# Rolab_PDD_prot.net
KiCad netlist of a schematic drawn in EAGLE
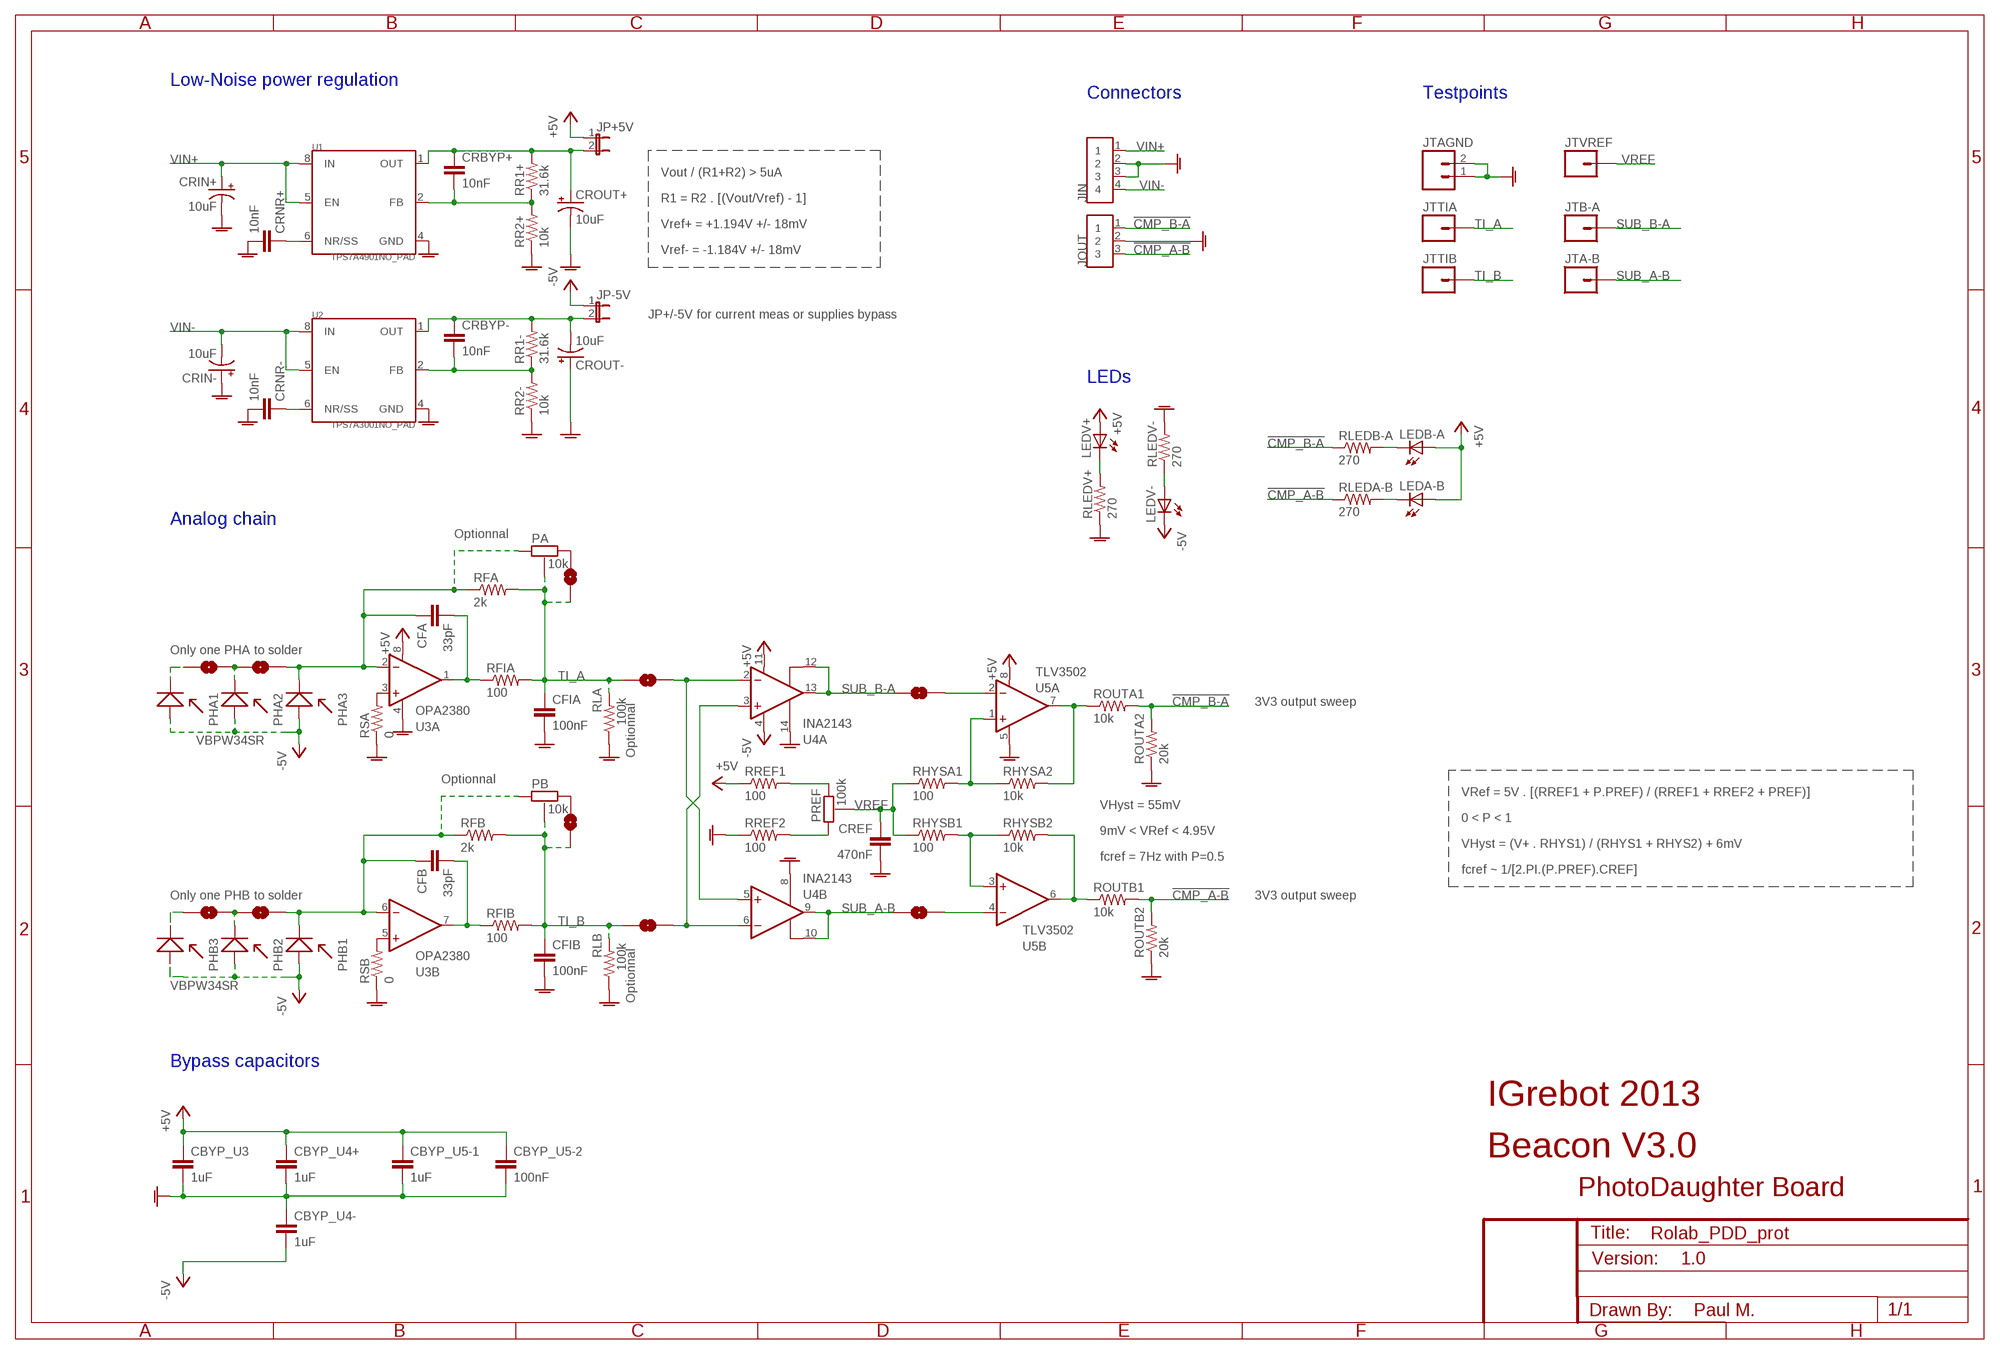
[diagram p0: schematic, sheet 1]

(export (version "E")
  (design (tool "Eeschema 10.0.6"))
  (components
    (comp (ref "CBYP_U3")
      (value "1uF")
      (footprint "eagle-import:0603-CAP")
      (libsource (lib "eagle-import") (part "CAP0603-CAP"))
    )
    (comp (ref "CBYP_U4+")
      (value "1uF")
      (footprint "eagle-import:0603-CAP")
      (libsource (lib "eagle-import") (part "CAP0603-CAP"))
    )
    (comp (ref "CBYP_U4-")
      (value "1uF")
      (footprint "eagle-import:0603-CAP")
      (libsource (lib "eagle-import") (part "CAP0603-CAP"))
    )
    (comp (ref "CBYP_U5-1")
      (value "1uF")
      (footprint "eagle-import:0603-CAP")
      (libsource (lib "eagle-import") (part "CAP0603-CAP"))
    )
    (comp (ref "CBYP_U5-2")
      (value "100nF")
      (footprint "eagle-import:0603-CAP")
      (libsource (lib "eagle-import") (part "CAP0603-CAP"))
    )
    (comp (ref "CFA")
      (value "33pF")
      (footprint "eagle-import:0603-CAP")
      (libsource (lib "eagle-import") (part "CAP0603-CAP"))
    )
    (comp (ref "CFB")
      (value "33pF")
      (footprint "eagle-import:0603-CAP")
      (libsource (lib "eagle-import") (part "CAP0603-CAP"))
    )
    (comp (ref "CFIA")
      (value "100nF")
      (footprint "eagle-import:0603-CAP")
      (libsource (lib "eagle-import") (part "CAP0603-CAP"))
    )
    (comp (ref "CFIB")
      (value "100nF")
      (footprint "eagle-import:0603-CAP")
      (libsource (lib "eagle-import") (part "CAP0603-CAP"))
    )
    (comp (ref "CRBYP+")
      (value "10nF")
      (footprint "eagle-import:0603-CAP")
      (libsource (lib "eagle-import") (part "CAP0603-CAP"))
    )
    (comp (ref "CRBYP-")
      (value "10nF")
      (footprint "eagle-import:0603-CAP")
      (libsource (lib "eagle-import") (part "CAP0603-CAP"))
    )
    (comp (ref "CREF")
      (value "470nF")
      (footprint "eagle-import:0603-CAP")
      (libsource (lib "eagle-import") (part "CAP0603-CAP"))
    )
    (comp (ref "CRIN+")
      (value "10uF")
      (footprint "eagle-import:EIA3528-KIT")
      (libsource (lib "eagle-import") (part "CAP_POL3528-KIT"))
    )
    (comp (ref "CRIN-")
      (value "10uF")
      (footprint "eagle-import:EIA3528-KIT")
      (libsource (lib "eagle-import") (part "CAP_POL3528-KIT"))
    )
    (comp (ref "CRNR+")
      (value "10nF")
      (footprint "eagle-import:0603-CAP")
      (libsource (lib "eagle-import") (part "CAP0603-CAP"))
    )
    (comp (ref "CRNR-")
      (value "10nF")
      (footprint "eagle-import:0603-CAP")
      (libsource (lib "eagle-import") (part "CAP0603-CAP"))
    )
    (comp (ref "CROUT+")
      (value "10uF")
      (footprint "eagle-import:EIA3528-KIT")
      (libsource (lib "eagle-import") (part "CAP_POL3528-KIT"))
    )
    (comp (ref "CROUT-")
      (value "10uF")
      (footprint "eagle-import:EIA3528-KIT")
      (libsource (lib "eagle-import") (part "CAP_POL3528-KIT"))
    )
    (comp (ref "JIN")
      (value "SIL4")
      (footprint "eagle-import:CON4-2.54")
      (libsource (lib "eagle-import") (part "SIL4"))
    )
    (comp (ref "JOUT")
      (value "SIL3")
      (footprint "eagle-import:CON3-2.54")
      (libsource (lib "eagle-import") (part "SIL3"))
    )
    (comp (ref "JP+5V")
      (value "JUMPER-2PTH_LOCK")
      (footprint "eagle-import:1X02_LOCK")
      (libsource (lib "eagle-import") (part "JUMPER-2PTH_LOCK"))
    )
    (comp (ref "JP-5V")
      (value "JUMPER-2PTH_LOCK")
      (footprint "eagle-import:1X02_LOCK")
      (libsource (lib "eagle-import") (part "JUMPER-2PTH_LOCK"))
    )
    (comp (ref "JTA-B")
      (value "M01PTH")
      (footprint "eagle-import:1X01")
      (libsource (lib "eagle-import") (part "M01PTH"))
    )
    (comp (ref "JTAGND")
      (value "M02LOCK")
      (footprint "eagle-import:1X02_LOCK")
      (libsource (lib "eagle-import") (part "M02LOCK"))
    )
    (comp (ref "JTB-A")
      (value "M01PTH")
      (footprint "eagle-import:1X01")
      (libsource (lib "eagle-import") (part "M01PTH"))
    )
    (comp (ref "JTTIA")
      (value "M01PTH")
      (footprint "eagle-import:1X01")
      (libsource (lib "eagle-import") (part "M01PTH"))
    )
    (comp (ref "JTTIB")
      (value "M01PTH")
      (footprint "eagle-import:1X01")
      (libsource (lib "eagle-import") (part "M01PTH"))
    )
    (comp (ref "JTVREF")
      (value "M01PTH")
      (footprint "eagle-import:1X01")
      (libsource (lib "eagle-import") (part "M01PTH"))
    )
    (comp (ref "LEDA-B")
      (value "LED0603")
      (footprint "eagle-import:LED-0603")
      (libsource (lib "eagle-import") (part "LED0603"))
    )
    (comp (ref "LEDB-A")
      (value "LED0603")
      (footprint "eagle-import:LED-0603")
      (libsource (lib "eagle-import") (part "LED0603"))
    )
    (comp (ref "LEDV+")
      (value "LED0603")
      (footprint "eagle-import:LED-0603")
      (libsource (lib "eagle-import") (part "LED0603"))
    )
    (comp (ref "LEDV-")
      (value "LED0603")
      (footprint "eagle-import:LED-0603")
      (libsource (lib "eagle-import") (part "LED0603"))
    )
    (comp (ref "PA")
      (value "10k")
      (footprint "eagle-import:TRIM-PVZ2A")
      (libsource (lib "eagle-import") (part "PVZ2A"))
    )
    (comp (ref "PB")
      (value "10k")
      (footprint "eagle-import:TRIM-PVZ2A")
      (libsource (lib "eagle-import") (part "PVZ2A"))
    )
    (comp (ref "PHA1")
      (value "VBPW34SR")
      (footprint "eagle-import:VBPW34SR")
      (libsource (lib "eagle-import") (part "VBPW34SR"))
    )
    (comp (ref "PHA2")
      (value "VBPW34SR")
      (footprint "eagle-import:VBPW34SR")
      (libsource (lib "eagle-import") (part "VBPW34SR"))
    )
    (comp (ref "PHA3")
      (value "VBPW34SR")
      (footprint "eagle-import:VBPW34SR")
      (libsource (lib "eagle-import") (part "VBPW34SR"))
    )
    (comp (ref "PHB1")
      (value "VBPW34SR")
      (footprint "eagle-import:VBPW34SR")
      (libsource (lib "eagle-import") (part "VBPW34SR"))
    )
    (comp (ref "PHB2")
      (value "VBPW34SR")
      (footprint "eagle-import:VBPW34SR")
      (libsource (lib "eagle-import") (part "VBPW34SR"))
    )
    (comp (ref "PHB3")
      (value "VBPW34SR")
      (footprint "eagle-import:VBPW34SR")
      (libsource (lib "eagle-import") (part "VBPW34SR"))
    )
    (comp (ref "PREF")
      (value "100k")
      (footprint "eagle-import:TRIM-PVZ2A")
      (libsource (lib "eagle-import") (part "PVZ2A"))
    )
    (comp (ref "RFA")
      (value "2k")
      (footprint "eagle-import:0603-RES")
      (libsource (lib "eagle-import") (part "RESISTOR0603-RES"))
    )
    (comp (ref "RFB")
      (value "2k")
      (footprint "eagle-import:0603-RES")
      (libsource (lib "eagle-import") (part "RESISTOR0603-RES"))
    )
    (comp (ref "RFIA")
      (value "100")
      (footprint "eagle-import:0603-RES")
      (libsource (lib "eagle-import") (part "RESISTOR0603-RES"))
    )
    (comp (ref "RFIB")
      (value "100")
      (footprint "eagle-import:0603-RES")
      (libsource (lib "eagle-import") (part "RESISTOR0603-RES"))
    )
    (comp (ref "RHYSA1")
      (value "100")
      (footprint "eagle-import:0603-RES")
      (libsource (lib "eagle-import") (part "RESISTOR0603-RES"))
    )
    (comp (ref "RHYSA2")
      (value "10k")
      (footprint "eagle-import:0603-RES")
      (libsource (lib "eagle-import") (part "RESISTOR0603-RES"))
    )
    (comp (ref "RHYSB1")
      (value "100")
      (footprint "eagle-import:0603-RES")
      (libsource (lib "eagle-import") (part "RESISTOR0603-RES"))
    )
    (comp (ref "RHYSB2")
      (value "10k")
      (footprint "eagle-import:0603-RES")
      (libsource (lib "eagle-import") (part "RESISTOR0603-RES"))
    )
    (comp (ref "RLA")
      (value "100k")
      (footprint "eagle-import:0603-RES")
      (libsource (lib "eagle-import") (part "RESISTOR0603-RES"))
    )
    (comp (ref "RLB")
      (value "100k")
      (footprint "eagle-import:0603-RES")
      (libsource (lib "eagle-import") (part "RESISTOR0603-RES"))
    )
    (comp (ref "RLEDA-B")
      (value "270")
      (footprint "eagle-import:0603-RES")
      (libsource (lib "eagle-import") (part "RESISTOR0603-RES"))
    )
    (comp (ref "RLEDB-A")
      (value "270")
      (footprint "eagle-import:0603-RES")
      (libsource (lib "eagle-import") (part "RESISTOR0603-RES"))
    )
    (comp (ref "RLEDV+")
      (value "270")
      (footprint "eagle-import:0603-RES")
      (libsource (lib "eagle-import") (part "RESISTOR0603-RES"))
    )
    (comp (ref "RLEDV-")
      (value "270")
      (footprint "eagle-import:0603-RES")
      (libsource (lib "eagle-import") (part "RESISTOR0603-RES"))
    )
    (comp (ref "ROUTA1")
      (value "10k")
      (footprint "eagle-import:0603-RES")
      (libsource (lib "eagle-import") (part "RESISTOR0603-RES"))
    )
    (comp (ref "ROUTA2")
      (value "20k")
      (footprint "eagle-import:0603-RES")
      (libsource (lib "eagle-import") (part "RESISTOR0603-RES"))
    )
    (comp (ref "ROUTB1")
      (value "10k")
      (footprint "eagle-import:0603-RES")
      (libsource (lib "eagle-import") (part "RESISTOR0603-RES"))
    )
    (comp (ref "ROUTB2")
      (value "20k")
      (footprint "eagle-import:0603-RES")
      (libsource (lib "eagle-import") (part "RESISTOR0603-RES"))
    )
    (comp (ref "RR1+")
      (value "31.6k")
      (footprint "eagle-import:0603-RES")
      (libsource (lib "eagle-import") (part "RESISTOR0603-RES"))
    )
    (comp (ref "RR1-")
      (value "31.6k")
      (footprint "eagle-import:0603-RES")
      (libsource (lib "eagle-import") (part "RESISTOR0603-RES"))
    )
    (comp (ref "RR2+")
      (value "10k")
      (footprint "eagle-import:0603-RES")
      (libsource (lib "eagle-import") (part "RESISTOR0603-RES"))
    )
    (comp (ref "RR2-")
      (value "10k")
      (footprint "eagle-import:0603-RES")
      (libsource (lib "eagle-import") (part "RESISTOR0603-RES"))
    )
    (comp (ref "RREF1")
      (value "100")
      (footprint "eagle-import:0603-RES")
      (libsource (lib "eagle-import") (part "RESISTOR0603-RES"))
    )
    (comp (ref "RREF2")
      (value "100")
      (footprint "eagle-import:0603-RES")
      (libsource (lib "eagle-import") (part "RESISTOR0603-RES"))
    )
    (comp (ref "RSA")
      (value "0")
      (footprint "eagle-import:0603-RES")
      (libsource (lib "eagle-import") (part "RESISTOR0603-RES"))
    )
    (comp (ref "RSB")
      (value "0")
      (footprint "eagle-import:0603-RES")
      (libsource (lib "eagle-import") (part "RESISTOR0603-RES"))
    )
    (comp (ref "SJ1")
      (value "SOLDERJUMPERNC")
      (footprint "eagle-import:SJ_2S")
      (libsource (lib "eagle-import") (part "SOLDERJUMPERNC"))
    )
    (comp (ref "SJ2")
      (value "SOLDERJUMPERNC")
      (footprint "eagle-import:SJ_2S")
      (libsource (lib "eagle-import") (part "SOLDERJUMPERNC"))
    )
    (comp (ref "SJ3")
      (value "SOLDERJUMPERNC")
      (footprint "eagle-import:SJ_2S")
      (libsource (lib "eagle-import") (part "SOLDERJUMPERNC"))
    )
    (comp (ref "SJ4")
      (value "SOLDERJUMPERNC")
      (footprint "eagle-import:SJ_2S")
      (libsource (lib "eagle-import") (part "SOLDERJUMPERNC"))
    )
    (comp (ref "SJ5")
      (value "SOLDERJUMPERNC")
      (footprint "eagle-import:SJ_2S")
      (libsource (lib "eagle-import") (part "SOLDERJUMPERNC"))
    )
    (comp (ref "SJ6")
      (value "SOLDERJUMPERNC")
      (footprint "eagle-import:SJ_2S")
      (libsource (lib "eagle-import") (part "SOLDERJUMPERNC"))
    )
    (comp (ref "SJ7")
      (value "SOLDERJUMPERNC")
      (footprint "eagle-import:SJ_2S")
      (libsource (lib "eagle-import") (part "SOLDERJUMPERNC"))
    )
    (comp (ref "SJ8")
      (value "SOLDERJUMPERNC")
      (footprint "eagle-import:SJ_2S")
      (libsource (lib "eagle-import") (part "SOLDERJUMPERNC"))
    )
    (comp (ref "SJ9")
      (value "SOLDERJUMPERNC")
      (footprint "eagle-import:SJ_2S")
      (libsource (lib "eagle-import") (part "SOLDERJUMPERNC"))
    )
    (comp (ref "SJ11")
      (value "SOLDERJUMPERNC")
      (footprint "eagle-import:SJ_2S")
      (libsource (lib "eagle-import") (part "SOLDERJUMPERNC"))
    )
    (comp (ref "U1")
      (value "TPS7A4901NO_PAD")
      (footprint "eagle-import:MSOP8")
      (libsource (lib "eagle-import") (part "TPS7A4901NO_PAD"))
    )
    (comp (ref "U2")
      (value "TPS7A3001NO_PAD")
      (footprint "eagle-import:MSOP8")
      (libsource (lib "eagle-import") (part "TPS7A3001NO_PAD"))
    )
    (comp (ref "U3")
      (value "OPA2380")
      (footprint "eagle-import:MSOP8")
      (libsource (lib "eagle-import") (part "OPA2380"))
    )
    (comp (ref "U4")
      (value "INA2143")
      (footprint "eagle-import:SOIC14")
      (libsource (lib "eagle-import") (part "INA2143"))
    )
    (comp (ref "U5")
      (value "TLV3502")
      (footprint "eagle-import:SOIC8")
      (libsource (lib "eagle-import") (part "TLV3502"))
    )
  )
  (nets
    (net (code "1") (name "+5V") (class "Default")
      (node (ref "CBYP_U3") (pin "1") (pinfunction "1_1") (pintype "passive"))
      (node (ref "CBYP_U4+") (pin "1") (pinfunction "1_1") (pintype "passive"))
      (node (ref "CBYP_U5-1") (pin "1") (pinfunction "1_1") (pintype "passive"))
      (node (ref "CBYP_U5-2") (pin "1") (pinfunction "1_1") (pintype "passive"))
      (node (ref "JP+5V") (pin "1") (pinfunction "1_1") (pintype "passive"))
      (node (ref "LEDA-B") (pin "A") (pinfunction "A_A") (pintype "passive"))
      (node (ref "LEDB-A") (pin "A") (pinfunction "A_A") (pintype "passive"))
      (node (ref "LEDV+") (pin "A") (pinfunction "A_A") (pintype "passive"))
      (node (ref "RREF1") (pin "1") (pinfunction "1_1") (pintype "passive"))
      (node (ref "U3") (pin "8") (pinfunction "V+_8") (pintype "power_in"))
      (node (ref "U4") (pin "11") (pinfunction "V+_11") (pintype "power_in"))
      (node (ref "U5") (pin "8") (pinfunction "V+_8") (pintype "power_in"))
    )
    (net (code "2") (name "-5V") (class "Default")
      (node (ref "CBYP_U4-") (pin "2") (pinfunction "2_2") (pintype "passive"))
      (node (ref "JP-5V") (pin "1") (pinfunction "1_1") (pintype "passive"))
      (node (ref "LEDV-") (pin "C") (pinfunction "C_C") (pintype "passive"))
      (node (ref "PHA1") (pin "A") (pinfunction "A_A") (pintype "bidirectional"))
      (node (ref "PHA2") (pin "A") (pinfunction "A_A") (pintype "bidirectional"))
      (node (ref "PHA3") (pin "A") (pinfunction "A_A") (pintype "bidirectional"))
      (node (ref "PHB1") (pin "A") (pinfunction "A_A") (pintype "bidirectional"))
      (node (ref "PHB2") (pin "A") (pinfunction "A_A") (pintype "bidirectional"))
      (node (ref "PHB3") (pin "A") (pinfunction "A_A") (pintype "bidirectional"))
      (node (ref "U4") (pin "4") (pinfunction "V-_4") (pintype "power_in"))
    )
    (net (code "3") (name "/SUB_A-B") (class "Default")
      (node (ref "JTA-B") (pin "1") (pinfunction "1_1") (pintype "passive"))
      (node (ref "SJ4") (pin "1") (pinfunction "1_1") (pintype "passive"))
      (node (ref "U4") (pin "10") (pinfunction "SENSE_10") (pintype "bidirectional"))
      (node (ref "U4") (pin "9") (pinfunction "OUT_9") (pintype "output"))
    )
    (net (code "4") (name "/SUB_B-A") (class "Default")
      (node (ref "JTB-A") (pin "1") (pinfunction "1_1") (pintype "passive"))
      (node (ref "SJ3") (pin "1") (pinfunction "1_1") (pintype "passive"))
      (node (ref "U4") (pin "12") (pinfunction "SENSE_12") (pintype "bidirectional"))
      (node (ref "U4") (pin "13") (pinfunction "OUT_13") (pintype "output"))
    )
    (net (code "5") (name "/TI_A") (class "Default")
      (node (ref "CFIA") (pin "1") (pinfunction "1_1") (pintype "passive"))
      (node (ref "JTTIA") (pin "1") (pinfunction "1_1") (pintype "passive"))
      (node (ref "PA") (pin "2") (pinfunction "B_2") (pintype "bidirectional"))
      (node (ref "RFA") (pin "2") (pinfunction "2_2") (pintype "passive"))
      (node (ref "RFIA") (pin "2") (pinfunction "2_2") (pintype "passive"))
      (node (ref "RLA") (pin "2") (pinfunction "2_2") (pintype "passive"))
      (node (ref "SJ1") (pin "1") (pinfunction "1_1") (pintype "passive"))
      (node (ref "SJ8") (pin "1") (pinfunction "1_1") (pintype "passive"))
    )
    (net (code "6") (name "/TI_B") (class "Default")
      (node (ref "CFIB") (pin "1") (pinfunction "1_1") (pintype "passive"))
      (node (ref "JTTIB") (pin "1") (pinfunction "1_1") (pintype "passive"))
      (node (ref "PB") (pin "2") (pinfunction "B_2") (pintype "bidirectional"))
      (node (ref "RFB") (pin "2") (pinfunction "2_2") (pintype "passive"))
      (node (ref "RFIB") (pin "2") (pinfunction "2_2") (pintype "passive"))
      (node (ref "RLB") (pin "2") (pinfunction "2_2") (pintype "passive"))
      (node (ref "SJ2") (pin "1") (pinfunction "1_1") (pintype "passive"))
      (node (ref "SJ6") (pin "1") (pinfunction "1_1") (pintype "passive"))
    )
    (net (code "7") (name "/VIN+") (class "Default")
      (node (ref "CRIN+") (pin "A") (pinfunction "+_A") (pintype "passive"))
      (node (ref "JIN") (pin "1") (pinfunction "1_1") (pintype "bidirectional"))
      (node (ref "U1") (pin "5") (pinfunction "EN_5") (pintype "input"))
      (node (ref "U1") (pin "8") (pinfunction "IN_8") (pintype "power_in"))
    )
    (net (code "8") (name "/VIN-") (class "Default")
      (node (ref "CRIN-") (pin "C") (pinfunction "-_C") (pintype "passive"))
      (node (ref "JIN") (pin "4") (pinfunction "4_4") (pintype "bidirectional"))
      (node (ref "U2") (pin "5") (pinfunction "EN_5") (pintype "input"))
      (node (ref "U2") (pin "8") (pinfunction "IN_8") (pintype "power_in"))
    )
    (net (code "9") (name "/VREF") (class "Default")
      (node (ref "CREF") (pin "1") (pinfunction "1_1") (pintype "passive"))
      (node (ref "JTVREF") (pin "1") (pinfunction "1_1") (pintype "passive"))
      (node (ref "PREF") (pin "2") (pinfunction "B_2") (pintype "bidirectional"))
      (node (ref "RHYSA1") (pin "1") (pinfunction "1_1") (pintype "passive"))
      (node (ref "RHYSB1") (pin "1") (pinfunction "1_1") (pintype "passive"))
    )
    (net (code "10") (name "/~{CMP_A-B}") (class "Default")
      (node (ref "JOUT") (pin "3") (pinfunction "3_3") (pintype "bidirectional"))
      (node (ref "RLEDA-B") (pin "1") (pinfunction "1_1") (pintype "passive"))
      (node (ref "ROUTB1") (pin "2") (pinfunction "2_2") (pintype "passive"))
      (node (ref "ROUTB2") (pin "2") (pinfunction "2_2") (pintype "passive"))
    )
    (net (code "11") (name "/~{CMP_B-A}") (class "Default")
      (node (ref "JOUT") (pin "1") (pinfunction "1_1") (pintype "bidirectional"))
      (node (ref "RLEDB-A") (pin "1") (pinfunction "1_1") (pintype "passive"))
      (node (ref "ROUTA1") (pin "2") (pinfunction "2_2") (pintype "passive"))
      (node (ref "ROUTA2") (pin "2") (pinfunction "2_2") (pintype "passive"))
    )
    (net (code "12") (name "AGND") (class "Default")
      (node (ref "CBYP_U3") (pin "2") (pinfunction "2_2") (pintype "passive"))
      (node (ref "CBYP_U4+") (pin "2") (pinfunction "2_2") (pintype "passive"))
      (node (ref "CBYP_U4-") (pin "1") (pinfunction "1_1") (pintype "passive"))
      (node (ref "CBYP_U5-1") (pin "2") (pinfunction "2_2") (pintype "passive"))
      (node (ref "CBYP_U5-2") (pin "2") (pinfunction "2_2") (pintype "passive"))
      (node (ref "CFIA") (pin "2") (pinfunction "2_2") (pintype "passive"))
      (node (ref "CFIB") (pin "2") (pinfunction "2_2") (pintype "passive"))
      (node (ref "CREF") (pin "2") (pinfunction "2_2") (pintype "passive"))
      (node (ref "CRIN+") (pin "C") (pinfunction "-_C") (pintype "passive"))
      (node (ref "CRIN-") (pin "A") (pinfunction "+_A") (pintype "passive"))
      (node (ref "CRNR+") (pin "2") (pinfunction "2_2") (pintype "passive"))
      (node (ref "CRNR-") (pin "2") (pinfunction "2_2") (pintype "passive"))
      (node (ref "CROUT+") (pin "C") (pinfunction "-_C") (pintype "passive"))
      (node (ref "CROUT-") (pin "A") (pinfunction "+_A") (pintype "passive"))
      (node (ref "JIN") (pin "2") (pinfunction "2_2") (pintype "bidirectional"))
      (node (ref "JIN") (pin "3") (pinfunction "3_3") (pintype "bidirectional"))
      (node (ref "JOUT") (pin "2") (pinfunction "2_2") (pintype "bidirectional"))
      (node (ref "JTAGND") (pin "1") (pinfunction "1_1") (pintype "passive"))
      (node (ref "JTAGND") (pin "2") (pinfunction "2_2") (pintype "passive"))
      (node (ref "RLA") (pin "1") (pinfunction "1_1") (pintype "passive"))
      (node (ref "RLB") (pin "1") (pinfunction "1_1") (pintype "passive"))
      (node (ref "RLEDV+") (pin "1") (pinfunction "1_1") (pintype "passive"))
      (node (ref "RLEDV-") (pin "2") (pinfunction "2_2") (pintype "passive"))
      (node (ref "ROUTA2") (pin "1") (pinfunction "1_1") (pintype "passive"))
      (node (ref "ROUTB2") (pin "1") (pinfunction "1_1") (pintype "passive"))
      (node (ref "RR2+") (pin "1") (pinfunction "1_1") (pintype "passive"))
      (node (ref "RR2-") (pin "1") (pinfunction "1_1") (pintype "passive"))
      (node (ref "RREF2") (pin "1") (pinfunction "1_1") (pintype "passive"))
      (node (ref "RSA") (pin "1") (pinfunction "1_1") (pintype "passive"))
      (node (ref "RSB") (pin "1") (pinfunction "1_1") (pintype "passive"))
      (node (ref "U1") (pin "4") (pinfunction "GND_4") (pintype "power_in"))
      (node (ref "U2") (pin "4") (pinfunction "GND_4") (pintype "power_in"))
      (node (ref "U3") (pin "4") (pinfunction "V-_4") (pintype "power_in"))
      (node (ref "U4") (pin "14") (pinfunction "REF_14") (pintype "input"))
      (node (ref "U4") (pin "8") (pinfunction "REF_8") (pintype "input"))
      (node (ref "U5") (pin "5") (pinfunction "V-_5") (pintype "power_in"))
    )
    (net (code "13") (name "Net-(CROUT+-+)") (class "Default")
      (node (ref "CRBYP+") (pin "1") (pinfunction "1_1") (pintype "passive"))
      (node (ref "CROUT+") (pin "A") (pinfunction "+_A") (pintype "passive"))
      (node (ref "JP+5V") (pin "2") (pinfunction "2_2") (pintype "passive"))
      (node (ref "RR1+") (pin "2") (pinfunction "2_2") (pintype "passive"))
      (node (ref "U1") (pin "1") (pinfunction "OUT_1") (pintype "power_in"))
    )
    (net (code "14") (name "Net-(CROUT---)") (class "Default")
      (node (ref "CRBYP-") (pin "1") (pinfunction "1_1") (pintype "passive"))
      (node (ref "CROUT-") (pin "C") (pinfunction "-_C") (pintype "passive"))
      (node (ref "JP-5V") (pin "2") (pinfunction "2_2") (pintype "passive"))
      (node (ref "RR1-") (pin "2") (pinfunction "2_2") (pintype "passive"))
      (node (ref "U2") (pin "1") (pinfunction "OUT_1") (pintype "power_in"))
    )
    (net (code "15") (name "Net-(LEDA-B-PadC)") (class "Default")
      (node (ref "LEDA-B") (pin "C") (pinfunction "C_C") (pintype "passive"))
      (node (ref "RLEDA-B") (pin "2") (pinfunction "2_2") (pintype "passive"))
    )
    (net (code "16") (name "Net-(LEDB-A-PadC)") (class "Default")
      (node (ref "LEDB-A") (pin "C") (pinfunction "C_C") (pintype "passive"))
      (node (ref "RLEDB-A") (pin "2") (pinfunction "2_2") (pintype "passive"))
    )
    (net (code "17") (name "Net-(LEDV+-PadC)") (class "Default")
      (node (ref "LEDV+") (pin "C") (pinfunction "C_C") (pintype "passive"))
      (node (ref "RLEDV+") (pin "2") (pinfunction "2_2") (pintype "passive"))
    )
    (net (code "18") (name "Net-(LEDV--PadA)") (class "Default")
      (node (ref "LEDV-") (pin "A") (pinfunction "A_A") (pintype "passive"))
      (node (ref "RLEDV-") (pin "1") (pinfunction "1_1") (pintype "passive"))
    )
    (net (code "19") (name "Net-(PA-A)") (class "Default")
      (node (ref "PA") (pin "1") (pinfunction "A_1") (pintype "bidirectional"))
      (node (ref "SJ8") (pin "2") (pinfunction "2_2") (pintype "passive"))
    )
    (net (code "20") (name "Net-(PA-C)") (class "Default")
      (node (ref "CFA") (pin "1") (pinfunction "1_1") (pintype "passive"))
      (node (ref "PA") (pin "3") (pinfunction "C_3") (pintype "bidirectional"))
      (node (ref "PHA3") (pin "K") (pinfunction "K_K") (pintype "bidirectional"))
      (node (ref "RFA") (pin "1") (pinfunction "1_1") (pintype "passive"))
      (node (ref "SJ7") (pin "2") (pinfunction "2_2") (pintype "passive"))
      (node (ref "U3") (pin "2") (pinfunction "-IN_2") (pintype "input"))
    )
    (net (code "21") (name "Net-(PB-A)") (class "Default")
      (node (ref "PB") (pin "1") (pinfunction "A_1") (pintype "bidirectional"))
      (node (ref "SJ6") (pin "2") (pinfunction "2_2") (pintype "passive"))
    )
    (net (code "22") (name "Net-(PB-C)") (class "Default")
      (node (ref "CFB") (pin "1") (pinfunction "1_1") (pintype "passive"))
      (node (ref "PB") (pin "3") (pinfunction "C_3") (pintype "bidirectional"))
      (node (ref "PHB1") (pin "K") (pinfunction "K_K") (pintype "bidirectional"))
      (node (ref "RFB") (pin "1") (pinfunction "1_1") (pintype "passive"))
      (node (ref "SJ5") (pin "2") (pinfunction "2_2") (pintype "passive"))
      (node (ref "U3") (pin "6") (pinfunction "-IN_6") (pintype "input"))
    )
    (net (code "23") (name "Net-(PHA1-PadK)") (class "Default")
      (node (ref "PHA1") (pin "K") (pinfunction "K_K") (pintype "bidirectional"))
      (node (ref "SJ11") (pin "1") (pinfunction "1_1") (pintype "passive"))
    )
    (net (code "24") (name "Net-(PHA2-PadK)") (class "Default")
      (node (ref "PHA2") (pin "K") (pinfunction "K_K") (pintype "bidirectional"))
      (node (ref "SJ11") (pin "2") (pinfunction "2_2") (pintype "passive"))
      (node (ref "SJ7") (pin "1") (pinfunction "1_1") (pintype "passive"))
    )
    (net (code "25") (name "Net-(PHB2-PadK)") (class "Default")
      (node (ref "PHB2") (pin "K") (pinfunction "K_K") (pintype "bidirectional"))
      (node (ref "SJ5") (pin "1") (pinfunction "1_1") (pintype "passive"))
      (node (ref "SJ9") (pin "2") (pinfunction "2_2") (pintype "passive"))
    )
    (net (code "26") (name "Net-(PHB3-PadK)") (class "Default")
      (node (ref "PHB3") (pin "K") (pinfunction "K_K") (pintype "bidirectional"))
      (node (ref "SJ9") (pin "1") (pinfunction "1_1") (pintype "passive"))
    )
    (net (code "27") (name "Net-(PREF-A)") (class "Default")
      (node (ref "PREF") (pin "1") (pinfunction "A_1") (pintype "bidirectional"))
      (node (ref "RREF1") (pin "2") (pinfunction "2_2") (pintype "passive"))
    )
    (net (code "28") (name "Net-(PREF-C)") (class "Default")
      (node (ref "PREF") (pin "3") (pinfunction "C_3") (pintype "bidirectional"))
      (node (ref "RREF2") (pin "2") (pinfunction "2_2") (pintype "passive"))
    )
    (net (code "29") (name "Net-(U1-FB)") (class "Default")
      (node (ref "CRBYP+") (pin "2") (pinfunction "2_2") (pintype "passive"))
      (node (ref "RR1+") (pin "1") (pinfunction "1_1") (pintype "passive"))
      (node (ref "RR2+") (pin "2") (pinfunction "2_2") (pintype "passive"))
      (node (ref "U1") (pin "2") (pinfunction "FB_2") (pintype "bidirectional"))
    )
    (net (code "30") (name "Net-(U1-NR{slash}SS)") (class "Default")
      (node (ref "CRNR+") (pin "1") (pinfunction "1_1") (pintype "passive"))
      (node (ref "U1") (pin "6") (pinfunction "NR/SS_6") (pintype "input"))
    )
    (net (code "31") (name "Net-(U2-FB)") (class "Default")
      (node (ref "CRBYP-") (pin "2") (pinfunction "2_2") (pintype "passive"))
      (node (ref "RR1-") (pin "1") (pinfunction "1_1") (pintype "passive"))
      (node (ref "RR2-") (pin "2") (pinfunction "2_2") (pintype "passive"))
      (node (ref "U2") (pin "2") (pinfunction "FB_2") (pintype "bidirectional"))
    )
    (net (code "32") (name "Net-(U2-NR{slash}SS)") (class "Default")
      (node (ref "CRNR-") (pin "1") (pinfunction "1_1") (pintype "passive"))
      (node (ref "U2") (pin "6") (pinfunction "NR/SS_6") (pintype "input"))
    )
    (net (code "33") (name "Net-(U3A-+IN)") (class "Default")
      (node (ref "RSA") (pin "2") (pinfunction "2_2") (pintype "passive"))
      (node (ref "U3") (pin "3") (pinfunction "+IN_3") (pintype "input"))
    )
    (net (code "34") (name "Net-(U3A-OUT)") (class "Default")
      (node (ref "CFA") (pin "2") (pinfunction "2_2") (pintype "passive"))
      (node (ref "RFIA") (pin "1") (pinfunction "1_1") (pintype "passive"))
      (node (ref "U3") (pin "1") (pinfunction "OUT_1") (pintype "output"))
    )
    (net (code "35") (name "Net-(U3B-+IN)") (class "Default")
      (node (ref "RSB") (pin "2") (pinfunction "2_2") (pintype "passive"))
      (node (ref "U3") (pin "5") (pinfunction "+IN_5") (pintype "input"))
    )
    (net (code "36") (name "Net-(U3B-OUT)") (class "Default")
      (node (ref "CFB") (pin "2") (pinfunction "2_2") (pintype "passive"))
      (node (ref "RFIB") (pin "1") (pinfunction "1_1") (pintype "passive"))
      (node (ref "U3") (pin "7") (pinfunction "OUT_7") (pintype "output"))
    )
    (net (code "37") (name "Net-(U4A-+IN)") (class "Default")
      (node (ref "SJ2") (pin "2") (pinfunction "2_2") (pintype "passive"))
      (node (ref "U4") (pin "3") (pinfunction "+IN_3") (pintype "input"))
      (node (ref "U4") (pin "6") (pinfunction "-IN_6") (pintype "input"))
    )
    (net (code "38") (name "Net-(U4A--IN)") (class "Default")
      (node (ref "SJ1") (pin "2") (pinfunction "2_2") (pintype "passive"))
      (node (ref "U4") (pin "2") (pinfunction "-IN_2") (pintype "input"))
      (node (ref "U4") (pin "5") (pinfunction "+IN_5") (pintype "input"))
    )
    (net (code "39") (name "Net-(U5A-+IN)") (class "Default")
      (node (ref "RHYSA1") (pin "2") (pinfunction "2_2") (pintype "passive"))
      (node (ref "RHYSA2") (pin "1") (pinfunction "1_1") (pintype "passive"))
      (node (ref "U5") (pin "1") (pinfunction "+IN_1") (pintype "input"))
    )
    (net (code "40") (name "Net-(U5A--IN)") (class "Default")
      (node (ref "SJ3") (pin "2") (pinfunction "2_2") (pintype "passive"))
      (node (ref "U5") (pin "2") (pinfunction "-IN_2") (pintype "input"))
    )
    (net (code "41") (name "Net-(U5A-OUT)") (class "Default")
      (node (ref "RHYSA2") (pin "2") (pinfunction "2_2") (pintype "passive"))
      (node (ref "ROUTA1") (pin "1") (pinfunction "1_1") (pintype "passive"))
      (node (ref "U5") (pin "7") (pinfunction "OUT_7") (pintype "output"))
    )
    (net (code "42") (name "Net-(U5B-+IN)") (class "Default")
      (node (ref "RHYSB1") (pin "2") (pinfunction "2_2") (pintype "passive"))
      (node (ref "RHYSB2") (pin "1") (pinfunction "1_1") (pintype "passive"))
      (node (ref "U5") (pin "3") (pinfunction "+IN_3") (pintype "input"))
    )
    (net (code "43") (name "Net-(U5B--IN)") (class "Default")
      (node (ref "SJ4") (pin "2") (pinfunction "2_2") (pintype "passive"))
      (node (ref "U5") (pin "4") (pinfunction "-IN_4") (pintype "input"))
    )
    (net (code "44") (name "Net-(U5B-OUT)") (class "Default")
      (node (ref "RHYSB2") (pin "2") (pinfunction "2_2") (pintype "passive"))
      (node (ref "ROUTB1") (pin "1") (pinfunction "1_1") (pintype "passive"))
      (node (ref "U5") (pin "6") (pinfunction "OUT_6") (pintype "output"))
    )
  )
)
